# top.net
KiCad netlist of a schematic drawn in Altium Designer
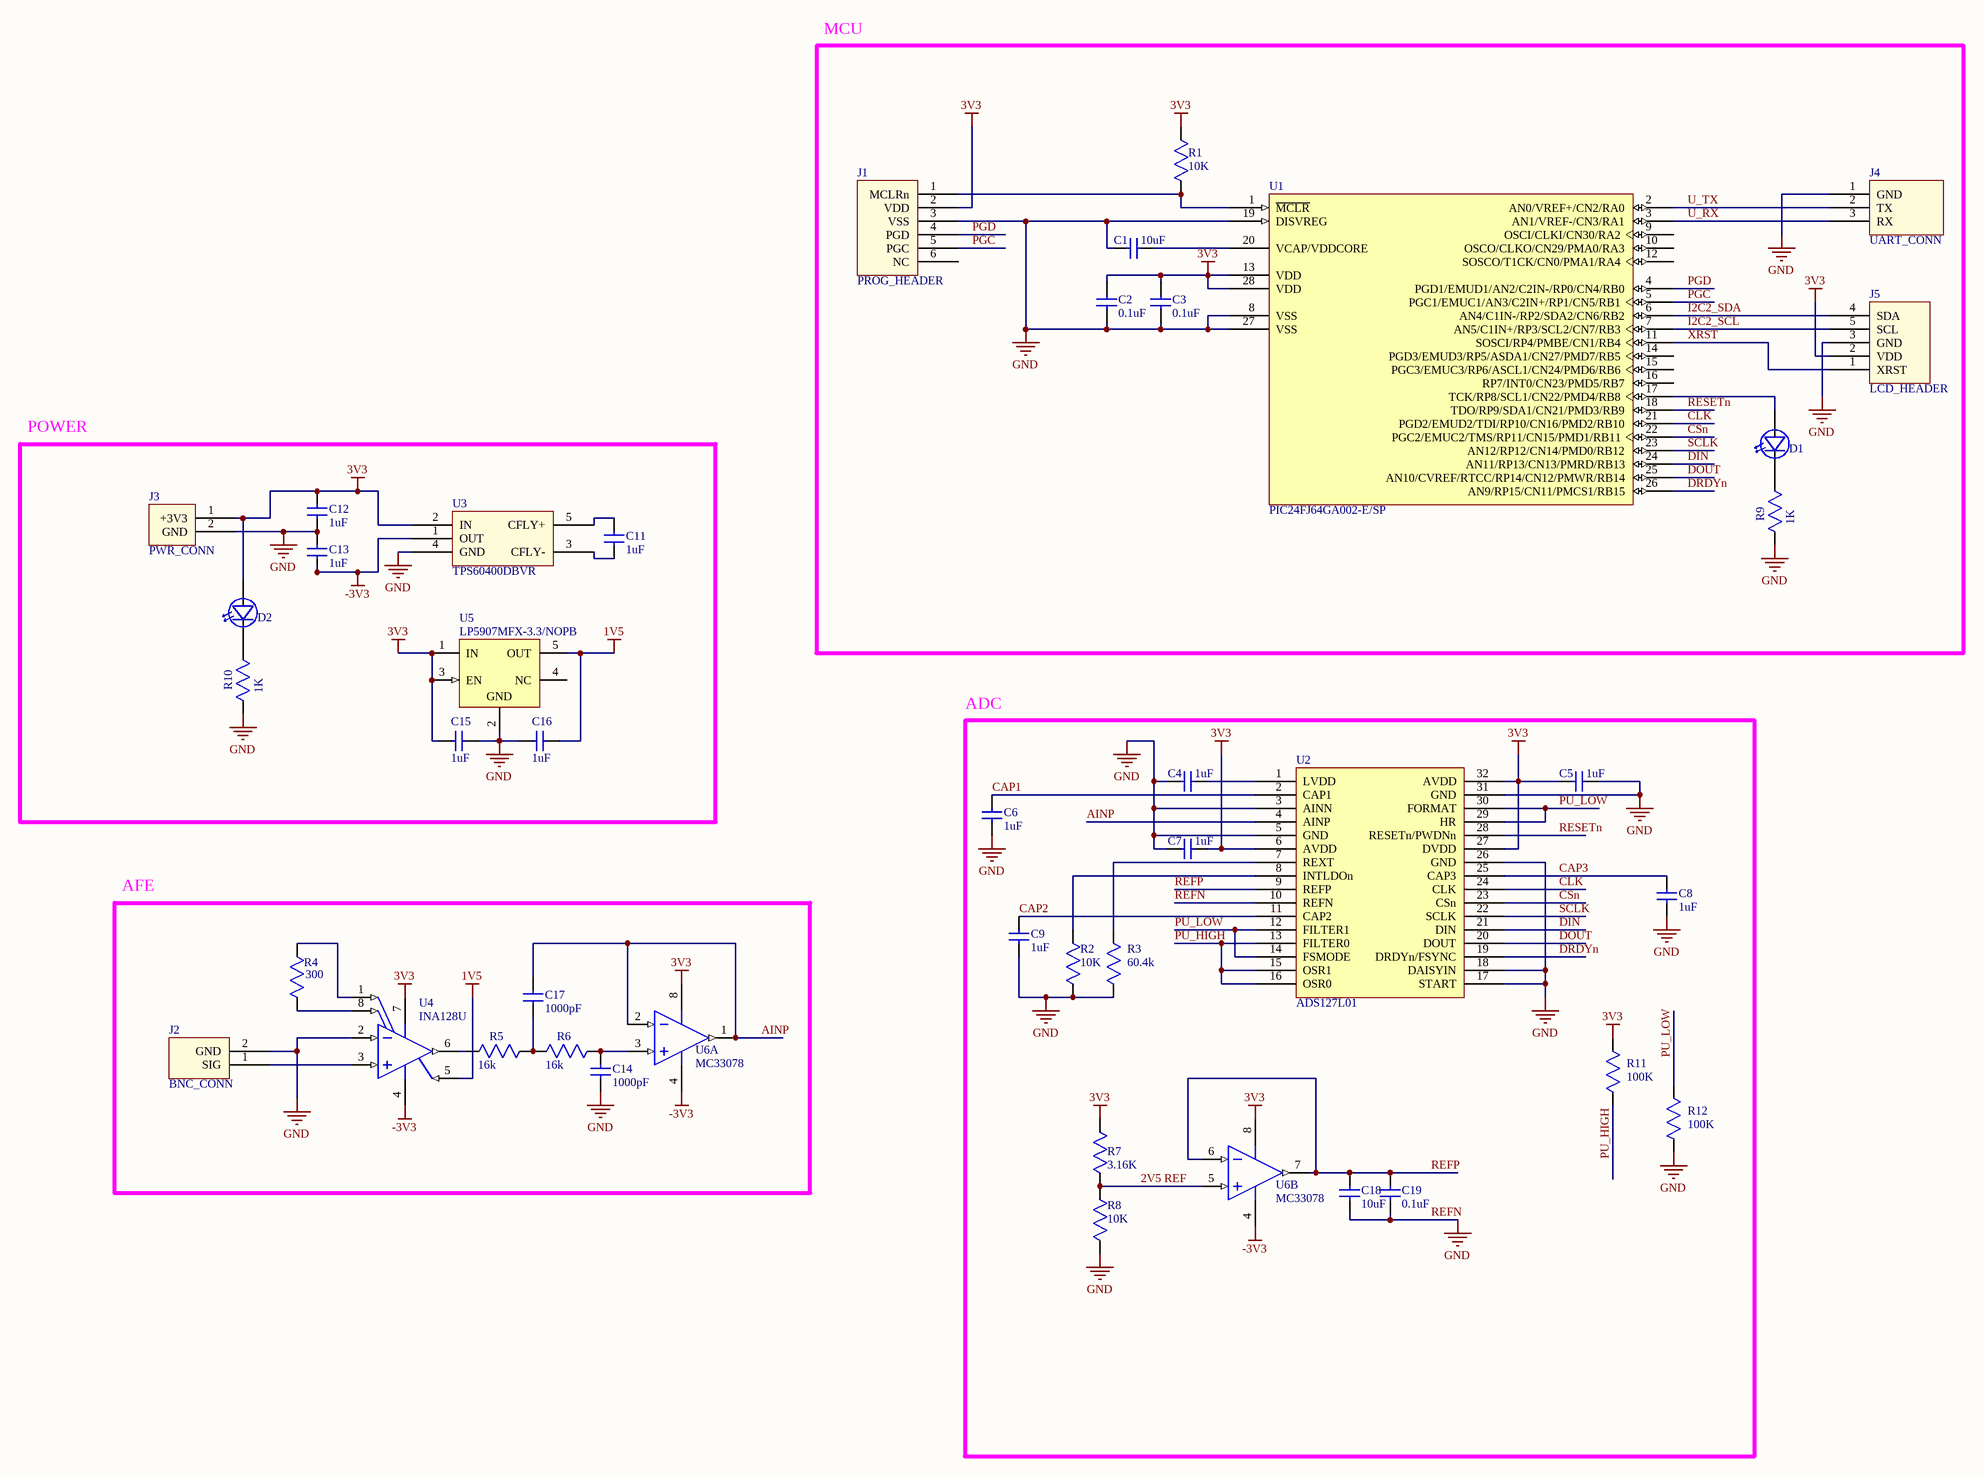
[diagram p0: top.SchDoc]

(export (version "E")
  (design (tool "Eeschema 10.0.6"))
  (components
    (comp (ref "C1")
      (value "10uF")
      (footprint "1210_Capacitor")
      (description "CAP CER 10UF 50V 10% X5R 1210")
      (fields
        (field (name "MANUFACTURER") "Taiyo Yuden")
        (field (name "Comment") "C_1210_10uF")
        (field (name "SVP CREATOR") "Matt Rogge")
      )
      (libsource (lib "Common") (part "C_1210_10uF"))
    )
    (comp (ref "C2")
      (value "0.1uF")
      (footprint "0805_Capacitor")
      (description "CAP CERM 0.1uF 10% 50V 0805")
      (fields
        (field (name "VOLTAGE") "50V")
        (field (name "Comment") "CAP 0.1uF 50V X7R")
        (field (name "SVP CREATOR") "Spencer Berglund")
      )
      (libsource (lib "Common") (part "C_0805_0.1uF_50V_10%"))
    )
    (comp (ref "C3")
      (value "0.1uF")
      (footprint "0805_Capacitor")
      (description "CAP CERM 0.1uF 10% 50V 0805")
      (fields
        (field (name "VOLTAGE") "50V")
        (field (name "Comment") "CAP 0.1uF 50V X7R")
        (field (name "SVP CREATOR") "Spencer Berglund")
      )
      (libsource (lib "Common") (part "C_0805_0.1uF_50V_10%"))
    )
    (comp (ref "C4")
      (value "1uF")
      (footprint "0805_Capacitor")
      (description "CAP CERM 1uF 10% 16V 0805")
      (fields
        (field (name "VOLTAGE") "16V")
        (field (name "Comment") "CAP 1uF 16V X7R")
        (field (name "SVP CREATOR") "Spencer Berglund")
      )
      (libsource (lib "Common") (part "C_0805_1uF_16V_10%"))
    )
    (comp (ref "C5")
      (value "1uF")
      (footprint "0805_Capacitor")
      (description "CAP CERM 1uF 10% 16V 0805")
      (fields
        (field (name "VOLTAGE") "16V")
        (field (name "Comment") "CAP 1uF 16V X7R")
        (field (name "SVP CREATOR") "Spencer Berglund")
      )
      (libsource (lib "Common") (part "C_0805_1uF_16V_10%"))
    )
    (comp (ref "C6")
      (value "1uF")
      (footprint "0805_Capacitor")
      (description "CAP CERM 1uF 10% 16V 0805")
      (fields
        (field (name "VOLTAGE") "16V")
        (field (name "Comment") "CAP 1uF 16V X7R")
        (field (name "SVP CREATOR") "Spencer Berglund")
      )
      (libsource (lib "Common") (part "C_0805_1uF_16V_10%"))
    )
    (comp (ref "C7")
      (value "1uF")
      (footprint "0805_Capacitor")
      (description "CAP CERM 1uF 10% 16V 0805")
      (fields
        (field (name "VOLTAGE") "16V")
        (field (name "Comment") "CAP 1uF 16V X7R")
        (field (name "SVP CREATOR") "Spencer Berglund")
      )
      (libsource (lib "Common") (part "C_0805_1uF_16V_10%"))
    )
    (comp (ref "C8")
      (value "1uF")
      (footprint "0805_Capacitor")
      (description "CAP CERM 1uF 10% 16V 0805")
      (fields
        (field (name "VOLTAGE") "16V")
        (field (name "Comment") "CAP 1uF 16V X7R")
        (field (name "SVP CREATOR") "Spencer Berglund")
      )
      (libsource (lib "Common") (part "C_0805_1uF_16V_10%"))
    )
    (comp (ref "C9")
      (value "1uF")
      (footprint "0805_Capacitor")
      (description "CAP CERM 1uF 10% 16V 0805")
      (fields
        (field (name "VOLTAGE") "16V")
        (field (name "Comment") "CAP 1uF 16V X7R")
        (field (name "SVP CREATOR") "Spencer Berglund")
      )
      (libsource (lib "Common") (part "C_0805_1uF_16V_10%"))
    )
    (comp (ref "C11")
      (value "1uF")
      (footprint "0805_Capacitor")
      (description "CAP CERM 1uF 10% 16V 0805")
      (fields
        (field (name "VOLTAGE") "16V")
        (field (name "Comment") "CAP 1uF 16V X7R")
        (field (name "SVP CREATOR") "Spencer Berglund")
      )
      (libsource (lib "Common") (part "C_0805_1uF_16V_10%"))
    )
    (comp (ref "C12")
      (value "1uF")
      (footprint "0805_Capacitor")
      (description "CAP CERM 1uF 10% 16V 0805")
      (fields
        (field (name "VOLTAGE") "16V")
        (field (name "Comment") "CAP 1uF 16V X7R")
        (field (name "SVP CREATOR") "Spencer Berglund")
      )
      (libsource (lib "Common") (part "C_0805_1uF_16V_10%"))
    )
    (comp (ref "C13")
      (value "1uF")
      (footprint "0805_Capacitor")
      (description "CAP CERM 1uF 10% 16V 0805")
      (fields
        (field (name "VOLTAGE") "16V")
        (field (name "Comment") "CAP 1uF 16V X7R")
        (field (name "SVP CREATOR") "Spencer Berglund")
      )
      (libsource (lib "Common") (part "C_0805_1uF_16V_10%"))
    )
    (comp (ref "C14")
      (value "1000pF")
      (footprint "0805_Capacitor")
      (description "CAP CERM 1000pF 10% 50V 0805")
      (fields
        (field (name "VOLTAGE") "50V")
        (field (name "Comment") "CAP 1000pF 50V X7R")
        (field (name "SVP CREATOR") "Spencer Berglund")
      )
      (libsource (lib "Common") (part "C_0805_1000pF_50V_10%"))
    )
    (comp (ref "C15")
      (value "1uF")
      (footprint "0805_Capacitor")
      (description "CAP CERM 1uF 10% 16V 0805")
      (fields
        (field (name "VOLTAGE") "16V")
        (field (name "Comment") "CAP 1uF 16V X7R")
        (field (name "SVP CREATOR") "Spencer Berglund")
      )
      (libsource (lib "Common") (part "C_0805_1uF_16V_10%"))
    )
    (comp (ref "C16")
      (value "1uF")
      (footprint "0805_Capacitor")
      (description "CAP CERM 1uF 10% 16V 0805")
      (fields
        (field (name "VOLTAGE") "16V")
        (field (name "Comment") "CAP 1uF 16V X7R")
        (field (name "SVP CREATOR") "Spencer Berglund")
      )
      (libsource (lib "Common") (part "C_0805_1uF_16V_10%"))
    )
    (comp (ref "C17")
      (value "1000pF")
      (footprint "0805_Capacitor")
      (description "CAP CERM 1000pF 10% 50V 0805")
      (fields
        (field (name "VOLTAGE") "50V")
        (field (name "Comment") "CAP 1000pF 50V X7R")
        (field (name "SVP CREATOR") "Spencer Berglund")
      )
      (libsource (lib "Common") (part "C_0805_1000pF_50V_10%"))
    )
    (comp (ref "C18")
      (value "10uF")
      (footprint "1210_Capacitor")
      (description "CAP CER 10UF 50V 10% X5R 1210")
      (fields
        (field (name "MANUFACTURER") "Taiyo Yuden")
        (field (name "Comment") "C_1210_10uF")
        (field (name "SVP CREATOR") "Matt Rogge")
      )
      (libsource (lib "Common") (part "C_1210_10uF"))
    )
    (comp (ref "C19")
      (value "0.1uF")
      (footprint "0805_Capacitor")
      (description "CAP CERM 0.1uF 10% 50V 0805")
      (fields
        (field (name "VOLTAGE") "50V")
        (field (name "Comment") "CAP 0.1uF 50V X7R")
        (field (name "SVP CREATOR") "Spencer Berglund")
      )
      (libsource (lib "Common") (part "C_0805_0.1uF_50V_10%"))
    )
    (comp (ref "D1")
      (value "D_LED_0805_BLUE")
      (footprint "0805_BLUE")
      (description "LED 2X1.2MM 470NM BL WTR CLR SMD")
      (fields (field (name "MANUFACTURER") "Kingbright") (field (name "SVP CREATOR") "Jonathan Nutzmann"))
      (libsource (lib "Common") (part "D_LED_0805_BLUE"))
    )
    (comp (ref "D2")
      (value "D_LED_0805_BLUE")
      (footprint "0805_BLUE")
      (description "LED 2X1.2MM 470NM BL WTR CLR SMD")
      (fields (field (name "MANUFACTURER") "Kingbright") (field (name "SVP CREATOR") "Jonathan Nutzmann"))
      (libsource (lib "Common") (part "D_LED_0805_BLUE"))
    )
    (comp (ref "J1")
      (value "PROG_HEADER")
      (footprint "PROG_HEADER")
      (description "For Programming the PIC24")
      (libsource (lib "ee3102_custom_components") (part "PROG_HEADER"))
    )
    (comp (ref "J2")
      (value "BNC_CONN")
      (footprint "BNC_Connector")
      (description "Connector for the noise input signal")
      (libsource (lib "ee3102_custom_components") (part "BNC_CONN"))
    )
    (comp (ref "J3")
      (value "PWR_CONN")
      (footprint "PJ-063AH")
      (libsource (lib "ee3102_custom_components") (part "PWR_CONN"))
    )
    (comp (ref "J4")
      (value "UART_CONN")
      (footprint "UART_HEADER")
      (description "Could be either a header or a USB Connector")
      (libsource (lib "ee3102_custom_components") (part "UART_CONN"))
    )
    (comp (ref "J5")
      (value "LCD_HEADER")
      (footprint "LCD Header")
      (libsource (lib "ee3102_custom_components") (part "LCD_HEADER"))
    )
    (comp (ref "R1")
      (value "10K")
      (footprint "0805_Resistor")
      (description "RES 10K OHM 1/8W 1% 0805 SMD")
      (fields (field (name "Comment") "R_0805_10K_1%") (field (name "SVP CREATOR") "Spencer Berglund"))
      (libsource (lib "Common") (part "R_0805_10K_1%"))
    )
    (comp (ref "R2")
      (value "10K")
      (footprint "0805_Resistor")
      (description "RES 10K OHM 1/8W 1% 0805 SMD")
      (fields (field (name "Comment") "R_0805_10K_1%") (field (name "SVP CREATOR") "Spencer Berglund"))
      (libsource (lib "Common") (part "R_0805_10K_1%"))
    )
    (comp (ref "R3")
      (value "60.4k")
      (footprint "0805_Resistor")
      (description "RES SMD 60.4K OHM 0.1% 1/8W 0805")
      (libsource (lib "ee3102_custom_components") (part "R_0805_60.4K_1%"))
    )
    (comp (ref "R4")
      (value "300")
      (footprint "0805_Resistor")
      (description "RES SMD 300 OHM 0.5% 1/10W 0805")
      (libsource (lib "ee3102_custom_components") (part "R_0805_300_0.5%"))
    )
    (comp (ref "R5")
      (value "16k")
      (footprint "0805_Resistor")
      (description "RES SMD 16K OHM 0.5% 1/10W 0805")
      (libsource (lib "ee3102_custom_components") (part "R_0805_16K_0.5%"))
    )
    (comp (ref "R6")
      (value "16k")
      (footprint "0805_Resistor")
      (description "RES SMD 16K OHM 0.5% 1/10W 0805")
      (libsource (lib "ee3102_custom_components") (part "R_0805_16K_0.5%"))
    )
    (comp (ref "R7")
      (value "3.16K")
      (footprint "0805_Resistor")
      (description "RES SMD 3.16K OHM 1% 1/8W 0805")
      (libsource (lib "ee3102_custom_components") (part "RES SMD 3.16K OHM 1% 1/8W 0805"))
    )
    (comp (ref "R8")
      (value "10K")
      (footprint "0805_Resistor")
      (description "RES 10K OHM 1/8W 1% 0805 SMD")
      (fields (field (name "Comment") "R_0805_10K_1%") (field (name "SVP CREATOR") "Spencer Berglund"))
      (libsource (lib "Common") (part "R_0805_10K_1%"))
    )
    (comp (ref "R9")
      (value "1K")
      (footprint "0805_Resistor")
      (description "RES 1K OHM 1/8W 1% 0805 SMD")
      (fields (field (name "Comment") "R_0805_1K_1%") (field (name "SVP CREATOR") "Spencer Berglund"))
      (libsource (lib "Common") (part "R_0805_1K_1%"))
    )
    (comp (ref "R10")
      (value "1K")
      (footprint "0805_Resistor")
      (description "RES 1K OHM 1/8W 1% 0805 SMD")
      (fields (field (name "Comment") "R_0805_1K_1%") (field (name "SVP CREATOR") "Spencer Berglund"))
      (libsource (lib "Common") (part "R_0805_1K_1%"))
    )
    (comp (ref "R11")
      (value "100K")
      (footprint "0805_Resistor")
      (description "RES 100K OHM 1/8W 1% 0805 SMD")
      (fields (field (name "Comment") "R_0805_100K_1%") (field (name "SVP CREATOR") "Spencer Berglund"))
      (libsource (lib "Common") (part "R_0805_100K_1%"))
    )
    (comp (ref "R12")
      (value "100K")
      (footprint "0805_Resistor")
      (description "RES 100K OHM 1/8W 1% 0805 SMD")
      (fields (field (name "Comment") "R_0805_100K_1%") (field (name "SVP CREATOR") "Spencer Berglund"))
      (libsource (lib "Common") (part "R_0805_100K_1%"))
    )
    (comp (ref "U1")
      (value "PIC24FJ64GA002-E/SP")
      (footprint "SPDIP300-SP28")
      (libsource (lib "Altium Content Vault") (part "MC-16B-16GA002-SOIC28"))
    )
    (comp (ref "U2")
      (value "ADS127L01")
      (footprint "TSQFP50P700X700X105-32N")
      (description "ADC")
      (libsource (lib "ee3102_custom_components") (part "ADS127L01"))
    )
    (comp (ref "U3")
      (value "TPS60400DBVR")
      (footprint "TPS60400DBVR")
      (description "IC REG SWTCHD CAP INV 60MA SOT23")
      (libsource (lib "ee3102_custom_components") (part "TPS60400DBVR"))
    )
    (comp (ref "U4")
      (value "INA128U")
      (footprint "D0008A_M")
      (fields (field (name "MANUFACTURER") "Texas Instruments"))
      (libsource (lib "Altium Content Vault") (part "TI-INA1XX-8"))
    )
    (comp (ref "U5")
      (value "LP5907MFX-3.3/NOPB")
      (footprint "DBV0005A_L")
      (fields (field (name "MANUFACTURER") "Texas Instruments"))
      (libsource (lib "Altium Content Vault") (part "TI-LP5907-SOT-23-5"))
    )
    (comp (ref "U6")
      (value "MC33078")
      (footprint "8-SOIC")
      (libsource (lib "ee3102_custom_components") (part "MC33078"))
    )
  )
  (nets
    (net (code "1") (name "-3V3") (class "Default")
      (node (ref "C13") (pin "1") (pinfunction "1_1") (pintype "passive"))
      (node (ref "U3") (pin "1") (pinfunction "OUT_1") (pintype "passive"))
      (node (ref "U4") (pin "4") (pinfunction "V-_4") (pintype "power_in"))
      (node (ref "U6") (pin "4") (pinfunction "VCC-_4") (pintype "power_in"))
    )
    (net (code "2") (name "/2V5 REF") (class "Default")
      (node (ref "R7") (pin "2") (pinfunction "2_2") (pintype "passive"))
      (node (ref "R8") (pin "1") (pinfunction "1_1") (pintype "passive"))
      (node (ref "U6") (pin "5") (pinfunction "IN2+_5") (pintype "input"))
    )
    (net (code "3") (name "/AINP") (class "Default")
      (node (ref "C17") (pin "1") (pinfunction "1_1") (pintype "passive"))
      (node (ref "U2") (pin "4") (pinfunction "AINP_4") (pintype "passive"))
      (node (ref "U6") (pin "1") (pinfunction "OUT1_1") (pintype "output"))
      (node (ref "U6") (pin "2") (pinfunction "IN1-_2") (pintype "input"))
    )
    (net (code "4") (name "/CAP1") (class "Default")
      (node (ref "C6") (pin "1") (pinfunction "1_1") (pintype "passive"))
      (node (ref "U2") (pin "2") (pinfunction "CAP1_2") (pintype "passive"))
    )
    (net (code "5") (name "/CAP2") (class "Default")
      (node (ref "C9") (pin "1") (pinfunction "1_1") (pintype "passive"))
      (node (ref "U2") (pin "11") (pinfunction "CAP2_11") (pintype "passive"))
    )
    (net (code "6") (name "/CAP3") (class "Default")
      (node (ref "C8") (pin "1") (pinfunction "1_1") (pintype "passive"))
      (node (ref "U2") (pin "25") (pinfunction "CAP3_25") (pintype "passive"))
    )
    (net (code "7") (name "/CLK") (class "Default")
      (node (ref "U1") (pin "21") (pinfunction "PGD2/EMUD2/TDI/RP10/CN16/PMD2/RB10_21") (pintype "bidirectional"))
      (node (ref "U2") (pin "24") (pinfunction "CLK_24") (pintype "passive"))
    )
    (net (code "8") (name "/CSn") (class "Default")
      (node (ref "U1") (pin "22") (pinfunction "PGC2/EMUC2/TMS/RP11/CN15/PMD1/RB11_22") (pintype "bidirectional"))
      (node (ref "U2") (pin "23") (pinfunction "CSn_23") (pintype "passive"))
    )
    (net (code "9") (name "/DIN") (class "Default")
      (node (ref "U1") (pin "24") (pinfunction "AN11/RP13/CN13/PMRD/RB13_24") (pintype "bidirectional"))
      (node (ref "U2") (pin "21") (pinfunction "DIN_21") (pintype "passive"))
    )
    (net (code "10") (name "/DOUT") (class "Default")
      (node (ref "U1") (pin "25") (pinfunction "AN10/CVREF/RTCC/RP14/CN12/PMWR/RB14_25") (pintype "bidirectional"))
      (node (ref "U2") (pin "20") (pinfunction "DOUT_20") (pintype "passive"))
    )
    (net (code "11") (name "/DRDYn") (class "Default")
      (node (ref "U1") (pin "26") (pinfunction "AN9/RP15/CN11/PMCS1/RB15_26") (pintype "bidirectional"))
      (node (ref "U2") (pin "19") (pinfunction "DRDYn/FSYNC_19") (pintype "passive"))
    )
    (net (code "12") (name "/I2C2_SCL") (class "Default")
      (node (ref "J5") (pin "5") (pinfunction "SCL_5") (pintype "passive"))
      (node (ref "U1") (pin "7") (pinfunction "AN5/C1IN+/RP3/SCL2/CN7/RB3_7") (pintype "bidirectional"))
    )
    (net (code "13") (name "/I2C2_SDA") (class "Default")
      (node (ref "J5") (pin "4") (pinfunction "SDA_4") (pintype "passive"))
      (node (ref "U1") (pin "6") (pinfunction "AN4/C1IN-/RP2/SDA2/CN6/RB2_6") (pintype "bidirectional"))
    )
    (net (code "14") (name "/PGC") (class "Default")
      (node (ref "J1") (pin "5") (pinfunction "PGC_5") (pintype "passive"))
      (node (ref "U1") (pin "5") (pinfunction "PGC1/EMUC1/AN3/C2IN+/RP1/CN5/RB1_5") (pintype "bidirectional"))
    )
    (net (code "15") (name "/PGD") (class "Default")
      (node (ref "J1") (pin "4") (pinfunction "PGD_4") (pintype "passive"))
      (node (ref "U1") (pin "4") (pinfunction "PGD1/EMUD1/AN2/C2IN-/RP0/CN4/RB0_4") (pintype "bidirectional"))
    )
    (net (code "16") (name "/PU_HIGH") (class "Default")
      (node (ref "R11") (pin "1") (pinfunction "1_1") (pintype "passive"))
      (node (ref "U2") (pin "13") (pinfunction "FILTER0_13") (pintype "passive"))
      (node (ref "U2") (pin "15") (pinfunction "OSR1_15") (pintype "passive"))
      (node (ref "U2") (pin "16") (pinfunction "OSR0_16") (pintype "passive"))
    )
    (net (code "17") (name "/PU_LOW") (class "Default")
      (node (ref "R12") (pin "1") (pinfunction "1_1") (pintype "passive"))
      (node (ref "U2") (pin "12") (pinfunction "FILTER1_12") (pintype "passive"))
      (node (ref "U2") (pin "14") (pinfunction "FSMODE_14") (pintype "passive"))
      (node (ref "U2") (pin "29") (pinfunction "HR_29") (pintype "passive"))
      (node (ref "U2") (pin "30") (pinfunction "FORMAT_30") (pintype "passive"))
    )
    (net (code "18") (name "/REFP") (class "Default")
      (node (ref "C18") (pin "1") (pinfunction "1_1") (pintype "passive"))
      (node (ref "C19") (pin "1") (pinfunction "1_1") (pintype "passive"))
      (node (ref "U2") (pin "9") (pinfunction "REFP_9") (pintype "passive"))
      (node (ref "U6") (pin "6") (pinfunction "IN2-_6") (pintype "input"))
      (node (ref "U6") (pin "7") (pinfunction "OUT2_7") (pintype "output"))
    )
    (net (code "19") (name "/RESETn") (class "Default")
      (node (ref "U1") (pin "18") (pinfunction "TDO/RP9/SDA1/CN21/PMD3/RB9_18") (pintype "bidirectional"))
      (node (ref "U2") (pin "28") (pinfunction "RESETn/PWDNn_28") (pintype "passive"))
    )
    (net (code "20") (name "/SCLK") (class "Default")
      (node (ref "U1") (pin "23") (pinfunction "AN12/RP12/CN14/PMD0/RB12_23") (pintype "bidirectional"))
      (node (ref "U2") (pin "22") (pinfunction "SCLK_22") (pintype "passive"))
    )
    (net (code "21") (name "/U_RX") (class "Default")
      (node (ref "J4") (pin "3") (pinfunction "RX_3") (pintype "passive"))
      (node (ref "U1") (pin "3") (pinfunction "AN1/VREF-/CN3/RA1_3") (pintype "bidirectional"))
    )
    (net (code "22") (name "/U_TX") (class "Default")
      (node (ref "J4") (pin "2") (pinfunction "TX_2") (pintype "passive"))
      (node (ref "U1") (pin "2") (pinfunction "AN0/VREF+/CN2/RA0_2") (pintype "bidirectional"))
    )
    (net (code "23") (name "/XRST") (class "Default")
      (node (ref "J5") (pin "1") (pinfunction "XRST_1") (pintype "passive"))
      (node (ref "U1") (pin "11") (pinfunction "SOSCI/RP4/PMBE/CN1/RB4_11") (pintype "bidirectional"))
    )
    (net (code "24") (name "1V5") (class "Default")
      (node (ref "C16") (pin "1") (pinfunction "1_1") (pintype "passive"))
      (node (ref "U4") (pin "5") (pinfunction "REF_5") (pintype "input"))
      (node (ref "U5") (pin "5") (pinfunction "OUT_5") (pintype "power_in"))
    )
    (net (code "25") (name "3V3") (class "Default")
      (node (ref "C12") (pin "2") (pinfunction "2_2") (pintype "passive"))
      (node (ref "C15") (pin "2") (pinfunction "2_2") (pintype "passive"))
      (node (ref "C2") (pin "1") (pinfunction "1_1") (pintype "passive"))
      (node (ref "C3") (pin "1") (pinfunction "1_1") (pintype "passive"))
      (node (ref "C5") (pin "1") (pinfunction "1_1") (pintype "passive"))
      (node (ref "C7") (pin "2") (pinfunction "2_2") (pintype "passive"))
      (node (ref "D2") (pin "2") (pinfunction "Anode_2") (pintype "passive"))
      (node (ref "J1") (pin "2") (pinfunction "VDD_2") (pintype "passive"))
      (node (ref "J3") (pin "1") (pinfunction "+3V3_1") (pintype "passive"))
      (node (ref "J5") (pin "2") (pinfunction "VDD_2") (pintype "passive"))
      (node (ref "R1") (pin "1") (pinfunction "1_1") (pintype "passive"))
      (node (ref "R11") (pin "2") (pinfunction "2_2") (pintype "passive"))
      (node (ref "R7") (pin "1") (pinfunction "1_1") (pintype "passive"))
      (node (ref "U1") (pin "13") (pinfunction "VDD_13") (pintype "power_in"))
      (node (ref "U1") (pin "28") (pinfunction "VDD_28") (pintype "power_in"))
      (node (ref "U2") (pin "27") (pinfunction "DVDD_27") (pintype "passive"))
      (node (ref "U2") (pin "32") (pinfunction "AVDD_32") (pintype "passive"))
      (node (ref "U2") (pin "6") (pinfunction "AVDD_6") (pintype "passive"))
      (node (ref "U3") (pin "2") (pinfunction "IN_2") (pintype "passive"))
      (node (ref "U4") (pin "7") (pinfunction "V+_7") (pintype "power_in"))
      (node (ref "U5") (pin "1") (pinfunction "IN_1") (pintype "power_in"))
      (node (ref "U5") (pin "3") (pinfunction "EN_3") (pintype "input"))
      (node (ref "U6") (pin "8") (pinfunction "VCC+_8") (pintype "power_in"))
    )
    (net (code "26") (name "GND") (class "Default")
      (node (ref "C1") (pin "2") (pinfunction "2_2") (pintype "passive"))
      (node (ref "C12") (pin "1") (pinfunction "1_1") (pintype "passive"))
      (node (ref "C13") (pin "2") (pinfunction "2_2") (pintype "passive"))
      (node (ref "C14") (pin "2") (pinfunction "2_2") (pintype "passive"))
      (node (ref "C15") (pin "1") (pinfunction "1_1") (pintype "passive"))
      (node (ref "C16") (pin "2") (pinfunction "2_2") (pintype "passive"))
      (node (ref "C18") (pin "2") (pinfunction "2_2") (pintype "passive"))
      (node (ref "C19") (pin "2") (pinfunction "2_2") (pintype "passive"))
      (node (ref "C2") (pin "2") (pinfunction "2_2") (pintype "passive"))
      (node (ref "C3") (pin "2") (pinfunction "2_2") (pintype "passive"))
      (node (ref "C4") (pin "1") (pinfunction "1_1") (pintype "passive"))
      (node (ref "C5") (pin "2") (pinfunction "2_2") (pintype "passive"))
      (node (ref "C6") (pin "2") (pinfunction "2_2") (pintype "passive"))
      (node (ref "C7") (pin "1") (pinfunction "1_1") (pintype "passive"))
      (node (ref "C8") (pin "2") (pinfunction "2_2") (pintype "passive"))
      (node (ref "C9") (pin "2") (pinfunction "2_2") (pintype "passive"))
      (node (ref "J1") (pin "3") (pinfunction "VSS_3") (pintype "passive"))
      (node (ref "J2") (pin "2") (pinfunction "GND_2") (pintype "passive"))
      (node (ref "J3") (pin "2") (pinfunction "GND_2") (pintype "passive"))
      (node (ref "J4") (pin "1") (pinfunction "GND_1") (pintype "passive"))
      (node (ref "J5") (pin "3") (pinfunction "GND_3") (pintype "passive"))
      (node (ref "R10") (pin "2") (pinfunction "2_2") (pintype "passive"))
      (node (ref "R12") (pin "2") (pinfunction "2_2") (pintype "passive"))
      (node (ref "R2") (pin "2") (pinfunction "2_2") (pintype "passive"))
      (node (ref "R3") (pin "2") (pinfunction "2_2") (pintype "passive"))
      (node (ref "R8") (pin "2") (pinfunction "2_2") (pintype "passive"))
      (node (ref "R9") (pin "2") (pinfunction "2_2") (pintype "passive"))
      (node (ref "U1") (pin "19") (pinfunction "DISVREG_19") (pintype "input"))
      (node (ref "U1") (pin "27") (pinfunction "VSS_27") (pintype "power_in"))
      (node (ref "U1") (pin "8") (pinfunction "VSS_8") (pintype "power_in"))
      (node (ref "U2") (pin "10") (pinfunction "REFN_10") (pintype "passive"))
      (node (ref "U2") (pin "17") (pinfunction "START_17") (pintype "passive"))
      (node (ref "U2") (pin "18") (pinfunction "DAISYIN_18") (pintype "passive"))
      (node (ref "U2") (pin "26") (pinfunction "GND_26") (pintype "passive"))
      (node (ref "U2") (pin "3") (pinfunction "AINN_3") (pintype "passive"))
      (node (ref "U2") (pin "31") (pinfunction "GND_31") (pintype "passive"))
      (node (ref "U2") (pin "5") (pinfunction "GND_5") (pintype "passive"))
      (node (ref "U3") (pin "4") (pinfunction "GND_4") (pintype "passive"))
      (node (ref "U4") (pin "2") (pinfunction "VIN-_2") (pintype "input"))
      (node (ref "U5") (pin "2") (pinfunction "GND_2") (pintype "power_in"))
    )
    (net (code "27") (name "Net-(C17-Pad2)") (class "Default")
      (node (ref "C17") (pin "2") (pinfunction "2_2") (pintype "passive"))
      (node (ref "R5") (pin "1") (pinfunction "1_1") (pintype "passive"))
      (node (ref "R6") (pin "2") (pinfunction "2_2") (pintype "passive"))
    )
    (net (code "28") (name "Net-(D1-Anode)") (class "Default")
      (node (ref "D1") (pin "2") (pinfunction "Anode_2") (pintype "passive"))
      (node (ref "U1") (pin "17") (pinfunction "TCK/RP8/SCL1/CN22/PMD4/RB8_17") (pintype "bidirectional"))
    )
    (net (code "29") (name "Net-(D1-Cathode)") (class "Default")
      (node (ref "D1") (pin "1") (pinfunction "Cathode_1") (pintype "passive"))
      (node (ref "R9") (pin "1") (pinfunction "1_1") (pintype "passive"))
    )
    (net (code "30") (name "Net-(D2-Cathode)") (class "Default")
      (node (ref "D2") (pin "1") (pinfunction "Cathode_1") (pintype "passive"))
      (node (ref "R10") (pin "1") (pinfunction "1_1") (pintype "passive"))
    )
    (net (code "31") (name "Net-(J1-MCLRn)") (class "Default")
      (node (ref "J1") (pin "1") (pinfunction "MCLRn_1") (pintype "passive"))
      (node (ref "R1") (pin "2") (pinfunction "2_2") (pintype "passive"))
      (node (ref "U1") (pin "1") (pinfunction "~{MCLR}_1") (pintype "input"))
    )
    (net (code "32") (name "Net-(J2-SIG)") (class "Default")
      (node (ref "J2") (pin "1") (pinfunction "SIG_1") (pintype "passive"))
      (node (ref "U4") (pin "3") (pinfunction "VIN+_3") (pintype "input"))
    )
    (net (code "33") (name "Net-(R4-Pad1)") (class "Default")
      (node (ref "R4") (pin "1") (pinfunction "1_1") (pintype "passive"))
      (node (ref "U4") (pin "1") (pinfunction "RG_1") (pintype "input"))
    )
    (net (code "34") (name "Net-(R4-Pad2)") (class "Default")
      (node (ref "R4") (pin "2") (pinfunction "2_2") (pintype "passive"))
      (node (ref "U4") (pin "8") (pinfunction "RG_8") (pintype "input"))
    )
    (net (code "35") (name "Net-(U1-VCAP{slash}VDDCORE)") (class "Default")
      (node (ref "C1") (pin "1") (pinfunction "1_1") (pintype "passive"))
      (node (ref "U1") (pin "20") (pinfunction "VCAP/VDDCORE_20") (pintype "power_in"))
    )
    (net (code "36") (name "Net-(U2-INTLDOn)") (class "Default")
      (node (ref "R2") (pin "1") (pinfunction "1_1") (pintype "passive"))
      (node (ref "U2") (pin "8") (pinfunction "INTLDOn_8") (pintype "passive"))
    )
    (net (code "37") (name "Net-(U2-LVDD)") (class "Default")
      (node (ref "C4") (pin "2") (pinfunction "2_2") (pintype "passive"))
      (node (ref "U2") (pin "1") (pinfunction "LVDD_1") (pintype "passive"))
    )
    (net (code "38") (name "Net-(U2-REXT)") (class "Default")
      (node (ref "R3") (pin "1") (pinfunction "1_1") (pintype "passive"))
      (node (ref "U2") (pin "7") (pinfunction "REXT_7") (pintype "passive"))
    )
    (net (code "39") (name "Net-(U3-CFLY+)") (class "Default")
      (node (ref "C11") (pin "2") (pinfunction "2_2") (pintype "passive"))
      (node (ref "U3") (pin "5") (pinfunction "CFLY+_5") (pintype "passive"))
    )
    (net (code "40") (name "Net-(U3-CFLY-)") (class "Default")
      (node (ref "C11") (pin "1") (pinfunction "1_1") (pintype "passive"))
      (node (ref "U3") (pin "3") (pinfunction "CFLY-_3") (pintype "passive"))
    )
    (net (code "41") (name "Net-(U4-VO)") (class "Default")
      (node (ref "R5") (pin "2") (pinfunction "2_2") (pintype "passive"))
      (node (ref "U4") (pin "6") (pinfunction "VO_6") (pintype "output"))
    )
    (net (code "42") (name "Net-(U6A-IN1+)") (class "Default")
      (node (ref "C14") (pin "1") (pinfunction "1_1") (pintype "passive"))
      (node (ref "R6") (pin "1") (pinfunction "1_1") (pintype "passive"))
      (node (ref "U6") (pin "3") (pinfunction "IN1+_3") (pintype "input"))
    )
    (net (code "43") (name "unconnected-(J1-NC-Pad6)") (class "Default")
      (node (ref "J1") (pin "6") (pinfunction "NC_6") (pintype "passive"))
    )
    (net (code "44") (name "unconnected-(U1-OSCI{slash}CLKI{slash}CN30{slash}RA2-Pad9)") (class "Default")
      (node (ref "U1") (pin "9") (pinfunction "OSCI/CLKI/CN30/RA2_9") (pintype "bidirectional"))
    )
    (net (code "45") (name "unconnected-(U1-OSCO{slash}CLKO{slash}CN29{slash}PMA0{slash}RA3-Pad10)") (class "Default")
      (node (ref "U1") (pin "10") (pinfunction "OSCO/CLKO/CN29/PMA0/RA3_10") (pintype "bidirectional"))
    )
    (net (code "46") (name "unconnected-(U1-PGC3{slash}EMUC3{slash}RP6{slash}ASCL1{slash}CN24{slash}PMD6{slash}RB6-Pad15)") (class "Default")
      (node (ref "U1") (pin "15") (pinfunction "PGC3/EMUC3/RP6/ASCL1/CN24/PMD6/RB6_15") (pintype "bidirectional"))
    )
    (net (code "47") (name "unconnected-(U1-PGD3{slash}EMUD3{slash}RP5{slash}ASDA1{slash}CN27{slash}PMD7{slash}RB5-Pad14)") (class "Default")
      (node (ref "U1") (pin "14") (pinfunction "PGD3/EMUD3/RP5/ASDA1/CN27/PMD7/RB5_14") (pintype "bidirectional"))
    )
    (net (code "48") (name "unconnected-(U1-RP7{slash}INT0{slash}CN23{slash}PMD5{slash}RB7-Pad16)") (class "Default")
      (node (ref "U1") (pin "16") (pinfunction "RP7/INT0/CN23/PMD5/RB7_16") (pintype "bidirectional"))
    )
    (net (code "49") (name "unconnected-(U1-SOSCO{slash}T1CK{slash}CN0{slash}PMA1{slash}RA4-Pad12)") (class "Default")
      (node (ref "U1") (pin "12") (pinfunction "SOSCO/T1CK/CN0/PMA1/RA4_12") (pintype "bidirectional"))
    )
    (net (code "50") (name "unconnected-(U5-NC-Pad4)") (class "Default")
      (node (ref "U5") (pin "4") (pinfunction "NC_4") (pintype "passive"))
    )
  )
)
